# HightKey.net
KiCad netlist of a schematic drawn in Altium Designer
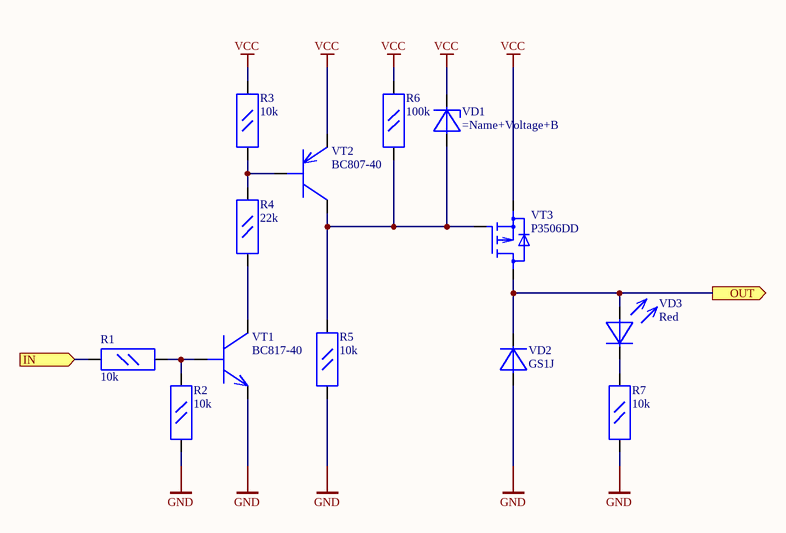
[diagram p0: HightKey.SchDoc]

(export (version "E")
  (design (tool "Eeschema 10.0.6"))
  (components
    (comp (ref "R1")
      (value "R0805")
      (footprint "RES0805")
      (description "Resistor")
      (fields (field (name "RESISTANCE (OHMS)") "10k"))
      (libsource (lib "zvemake_int_lib") (part "R0805"))
    )
    (comp (ref "R2")
      (value "R0805")
      (footprint "RES0805")
      (description "Resistor")
      (fields (field (name "RESISTANCE (OHMS)") "10k"))
      (libsource (lib "zvemake_int_lib") (part "R0805"))
    )
    (comp (ref "R3")
      (value "R0805")
      (footprint "RES0805")
      (description "Resistor")
      (fields (field (name "RESISTANCE (OHMS)") "10k"))
      (libsource (lib "zvemake_int_lib") (part "R0805"))
    )
    (comp (ref "R4")
      (value "R0805")
      (footprint "RES0805")
      (description "Resistor")
      (fields (field (name "RESISTANCE (OHMS)") "22k"))
      (libsource (lib "zvemake_int_lib") (part "R0805"))
    )
    (comp (ref "R5")
      (value "R0805")
      (footprint "RES0805")
      (description "Resistor")
      (fields (field (name "RESISTANCE (OHMS)") "10k"))
      (libsource (lib "zvemake_int_lib") (part "R0805"))
    )
    (comp (ref "R6")
      (value "R0805")
      (footprint "RES0805")
      (description "Resistor")
      (fields (field (name "RESISTANCE (OHMS)") "100k"))
      (libsource (lib "zvemake_int_lib") (part "R0805"))
    )
    (comp (ref "R7")
      (value "R0805")
      (footprint "RES0805")
      (description "Resistor")
      (fields (field (name "RESISTANCE (OHMS)") "10k"))
      (libsource (lib "zvemake_int_lib") (part "R0805"))
    )
    (comp (ref "VD1")
      (value "PDZ12")
      (footprint "SOD323")
      (description "Diode")
      (fields (field (name "VOLTAGE") "12"))
      (libsource (lib "zvemake_int_lib") (part "PDZ-B"))
    )
    (comp (ref "VD2")
      (value "GS1J")
      (footprint "DO-214AC(SMA)")
      (description "1.0A Surface Mount Standard Diode")
      (fields (field (name "VOLTAGE") "600V") (field (name "MANUFACTURER") "WTE"))
      (libsource (lib "zvemake_int_lib") (part "GS1J"))
    )
    (comp (ref "VD3")
      (value "Led Red 3mm")
      (footprint "3mm led red")
      (description "3mm Red Led 2.54pitch")
      (fields (field (name "COLOR") "Red"))
      (libsource (lib "zvemake_int_lib") (part "Led Red 3mm"))
    )
    (comp (ref "VT1")
      (value "BC817-40")
      (footprint "SOT95P230X110-3N")
      (description "NPN bipolar transistor")
      (libsource (lib "zvemake_int_lib") (part "BC817-40"))
    )
    (comp (ref "VT2")
      (value "BC807-40")
      (footprint "SOT95P230X110-3N")
      (description "PNP bipolar transistor")
      (libsource (lib "zvemake_int_lib") (part "BC807-40"))
    )
    (comp (ref "VT3")
      (value "P3506DD")
      (footprint "DPAK")
      (description "P-channel MOSFET transistor")
      (fields (field (name "MANUFACTURER") "NIKO SEMICONDUCTOR CO"))
      (libsource (lib "zvemake_int_lib") (part "P3506DD"))
    )
  )
  (nets
    (net (code "1") (name "/IN") (class "Default")
      (node (ref "R1") (pin "1") (pinfunction "1_1") (pintype "passive"))
    )
    (net (code "2") (name "/OUT") (class "Default")
      (node (ref "VD2") (pin "1") (pinfunction "C_1") (pintype "passive"))
      (node (ref "VD3") (pin "2") (pinfunction "A_2") (pintype "passive"))
      (node (ref "VT3") (pin "2") (pinfunction "D_2") (pintype "passive"))
    )
    (net (code "3") (name "GND") (class "Default")
      (node (ref "R2") (pin "1") (pinfunction "1_1") (pintype "passive"))
      (node (ref "R5") (pin "1") (pinfunction "1_1") (pintype "passive"))
      (node (ref "R7") (pin "1") (pinfunction "1_1") (pintype "passive"))
      (node (ref "VD2") (pin "2") (pinfunction "A_2") (pintype "passive"))
      (node (ref "VT1") (pin "2") (pinfunction "E_2") (pintype "passive"))
    )
    (net (code "4") (name "Net-(VD1-A)") (class "Default")
      (node (ref "R5") (pin "2") (pinfunction "2_2") (pintype "passive"))
      (node (ref "R6") (pin "1") (pinfunction "1_1") (pintype "passive"))
      (node (ref "VD1") (pin "2") (pinfunction "A_2") (pintype "passive"))
      (node (ref "VT2") (pin "3") (pinfunction "C_3") (pintype "passive"))
      (node (ref "VT3") (pin "1") (pinfunction "G_1") (pintype "passive"))
    )
    (net (code "5") (name "Net-(VD3-C)") (class "Default")
      (node (ref "R7") (pin "2") (pinfunction "2_2") (pintype "passive"))
      (node (ref "VD3") (pin "1") (pinfunction "C_1") (pintype "passive"))
    )
    (net (code "6") (name "Net-(VT1-B)") (class "Default")
      (node (ref "R1") (pin "2") (pinfunction "2_2") (pintype "passive"))
      (node (ref "R2") (pin "2") (pinfunction "2_2") (pintype "passive"))
      (node (ref "VT1") (pin "1") (pinfunction "B_1") (pintype "passive"))
    )
    (net (code "7") (name "Net-(VT1-C)") (class "Default")
      (node (ref "R4") (pin "1") (pinfunction "1_1") (pintype "passive"))
      (node (ref "VT1") (pin "3") (pinfunction "C_3") (pintype "passive"))
    )
    (net (code "8") (name "Net-(VT2-B)") (class "Default")
      (node (ref "R3") (pin "1") (pinfunction "1_1") (pintype "passive"))
      (node (ref "R4") (pin "2") (pinfunction "2_2") (pintype "passive"))
      (node (ref "VT2") (pin "1") (pinfunction "B_1") (pintype "passive"))
    )
    (net (code "9") (name "VCC") (class "Default")
      (node (ref "R3") (pin "2") (pinfunction "2_2") (pintype "passive"))
      (node (ref "R6") (pin "2") (pinfunction "2_2") (pintype "passive"))
      (node (ref "VD1") (pin "1") (pinfunction "C_1") (pintype "passive"))
      (node (ref "VT2") (pin "2") (pinfunction "E_2") (pintype "passive"))
      (node (ref "VT3") (pin "3") (pinfunction "S_3") (pintype "passive"))
    )
  )
)
